# USB.net
KiCad netlist of a schematic drawn in Altium Designer
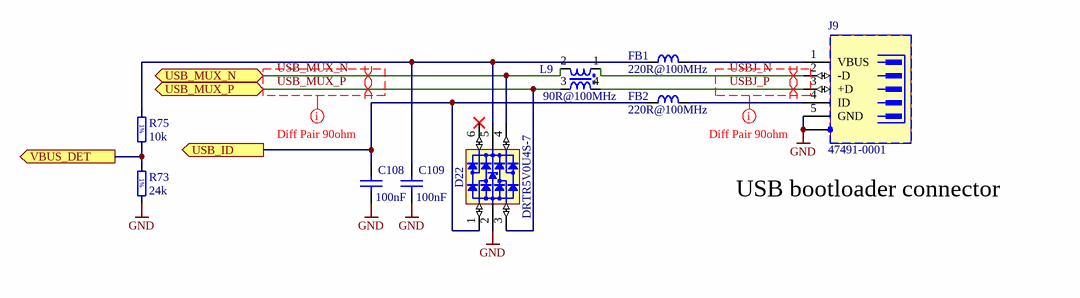
[diagram p0: USB.SchDoc]

(export (version "E")
  (design (tool "Eeschema 10.0.6"))
  (components
    (comp (ref "C108")
      (value "100nF")
      (footprint "CAPC1005X55N")
      (description "Non-polarised capacitor")
      (fields
        (field (name "PART NUMBER") "CC0402_100NF_16V_10%_X5R")
        (field (name "VOLTAGE") "16V")
        (field (name "AUTHOR") "CERN DEM JLC")
      )
      (libsource (lib "Capacitors") (part "Capacitor - non polarized"))
    )
    (comp (ref "C109")
      (value "100nF")
      (footprint "CAPC1005X55N")
      (description "Non-polarised capacitor")
      (fields
        (field (name "PART NUMBER") "CC0402_100NF_16V_10%_X5R")
        (field (name "VOLTAGE") "16V")
        (field (name "AUTHOR") "CERN DEM JLC")
      )
      (libsource (lib "Capacitors") (part "Capacitor - non polarized"))
    )
    (comp (ref "D22")
      (value "DRTR5V0U4S-7")
      (footprint "SOT65P210X110-6N")
      (description "Integrated Quad Ultra-Low Capacitance ESD Protection")
      (fields (field (name "MANUFACTURER") "DIODES") (field (name "AUTHOR") "GK"))
      (libsource (lib "Diodes") (part "D_TVS_DRTR5V0U4S-7"))
    )
    (comp (ref "FB1")
      (value "220R@100MHz")
      (footprint "INDC2012X105N")
      (description "Inductor")
      (fields
        (field (name "PART NUMBER") "IND0805_MURATA_BLM21PG221SN1D")
        (field (name "POWER") "2A")
        (field (name "AUTHOR") "CERN DEM JLC")
      )
      (libsource (lib "Inductors & Transformers") (part "Inductor"))
    )
    (comp (ref "FB2")
      (value "220R@100MHz")
      (footprint "INDC2012X105N")
      (description "Inductor")
      (fields
        (field (name "PART NUMBER") "IND0805_MURATA_BLM21PG221SN1D")
        (field (name "POWER") "2A")
        (field (name "AUTHOR") "CERN DEM JLC")
      )
      (libsource (lib "Inductors & Transformers") (part "Inductor"))
    )
    (comp (ref "J9")
      (value "Conn_Molex_47491-0001_eec")
      (footprint "Molex_47491-0001_0")
      (description "CONN RCPT 5POS MICRO USB R/A")
      (fields
        (field (name "MANUFACTURER") "Molex")
        (field (name "MOUSER PART NUMBER") "538-47491-0001")
        (field (name "MANUFACTURER PART NUMBER") "47491-0001")
      )
      (libsource (lib "Conn_Molex_47491-0001_eec") (part "Conn_Molex_47491-0001_eec"))
    )
    (comp (ref "L9")
      (value "90R@100MHz")
      (footprint "IND_MURATA_DLW21S")
      (description "Inductor Common Mode")
      (fields
        (field (name "PART NUMBER") "IND_MURATA_DLW21SN900SQ2L")
        (field (name "POWER") "330mA")
        (field (name "AUTHOR") "CERN DEM JLC")
      )
      (libsource (lib "Inductors & Transformers") (part "Inductor Common Mode 1Dot-2 4Dot-3"))
    )
    (comp (ref "R73")
      (value "24k")
      (footprint "RESC1608X55N")
      (description "Resistor - 1%")
      (fields
        (field (name "PART NUMBER") "R0603_24K_1%_0.1W_100PPM")
        (field (name "POWER") "0.1W")
        (field (name "AUTHOR") "CERN DEM JLC")
      )
      (libsource (lib "Resistors") (part "Resistor - 1%"))
    )
    (comp (ref "R75")
      (value "10k")
      (footprint "RESC1005X40N")
      (description "Resistor - 1%")
      (fields
        (field (name "PART NUMBER") "R0402_10K_1%_0.0625W_100PPM")
        (field (name "POWER") "0.0625W")
        (field (name "AUTHOR") "CERN DEM JLC")
      )
      (libsource (lib "Resistors") (part "Resistor - 1%"))
    )
  )
  (nets
    (net (code "1") (name "/USBJ_N") (class "Default")
      (node (ref "J9") (pin "2") (pinfunction "-D_2") (pintype "bidirectional"))
      (node (ref "L9") (pin "1") (pinfunction "1_1") (pintype "passive"))
    )
    (net (code "2") (name "/USBJ_P") (class "Default")
      (node (ref "J9") (pin "3") (pinfunction "+D_3") (pintype "bidirectional"))
      (node (ref "L9") (pin "4") (pinfunction "4_4") (pintype "passive"))
    )
    (net (code "3") (name "/USB_ID") (class "Default")
      (node (ref "C108") (pin "2") (pinfunction "2_2") (pintype "passive"))
      (node (ref "D22") (pin "1") (pinfunction "I/O1_1") (pintype "bidirectional"))
      (node (ref "FB2") (pin "1") (pinfunction "1_1") (pintype "passive"))
    )
    (net (code "4") (name "/USB_MUX_N") (class "Default")
      (node (ref "D22") (pin "4") (pinfunction "I/O3_4") (pintype "bidirectional"))
      (node (ref "L9") (pin "2") (pinfunction "2_2") (pintype "passive"))
    )
    (net (code "5") (name "/USB_MUX_P") (class "Default")
      (node (ref "D22") (pin "3") (pinfunction "I/O2_3") (pintype "bidirectional"))
      (node (ref "L9") (pin "3") (pinfunction "3_3") (pintype "passive"))
    )
    (net (code "6") (name "/VBUS_DET") (class "Default")
      (node (ref "R73") (pin "1") (pinfunction "1_1") (pintype "passive"))
      (node (ref "R75") (pin "2") (pinfunction "2_2") (pintype "passive"))
    )
    (net (code "7") (name "GND") (class "Default")
      (node (ref "C108") (pin "1") (pinfunction "1_1") (pintype "passive"))
      (node (ref "C109") (pin "1") (pinfunction "1_1") (pintype "passive"))
      (node (ref "D22") (pin "2") (pinfunction "GND_2") (pintype "power_in"))
      (node (ref "J9") (pin "10") (pinfunction "MNT_5_10") (pintype "passive"))
      (node (ref "J9") (pin "11") (pinfunction "MNT_6_11") (pintype "passive"))
      (node (ref "J9") (pin "5") (pinfunction "GND_5") (pintype "power_in"))
      (node (ref "J9") (pin "6") (pinfunction "SH_6") (pintype "power_in"))
      (node (ref "J9") (pin "7") (pinfunction "MNT_2_7") (pintype "passive"))
      (node (ref "J9") (pin "8") (pinfunction "MNT_3_8") (pintype "passive"))
      (node (ref "J9") (pin "9") (pinfunction "MNT_4_9") (pintype "passive"))
      (node (ref "R73") (pin "2") (pinfunction "2_2") (pintype "passive"))
    )
    (net (code "8") (name "Net-(D22-VBUS)") (class "Default")
      (node (ref "C109") (pin "2") (pinfunction "2_2") (pintype "passive"))
      (node (ref "D22") (pin "5") (pinfunction "VBUS_5") (pintype "power_in"))
      (node (ref "FB1") (pin "1") (pinfunction "1_1") (pintype "passive"))
      (node (ref "R75") (pin "1") (pinfunction "1_1") (pintype "passive"))
    )
    (net (code "9") (name "Net-(J9-ID)") (class "Default")
      (node (ref "FB2") (pin "2") (pinfunction "2_2") (pintype "passive"))
      (node (ref "J9") (pin "4") (pinfunction "ID_4") (pintype "passive"))
    )
    (net (code "10") (name "Net-(J9-VBUS)") (class "Default")
      (node (ref "FB1") (pin "2") (pinfunction "2_2") (pintype "passive"))
      (node (ref "J9") (pin "1") (pinfunction "VBUS_1") (pintype "power_in"))
    )
    (net (code "11") (name "unconnected-(D22-I{slash}O4-Pad6)") (class "Default")
      (node (ref "D22") (pin "6") (pinfunction "I/O4_6") (pintype "bidirectional+no_connect"))
    )
  )
)
